# Serial_Wire_Debug.net
KiCad netlist of a schematic drawn in Altium Designer
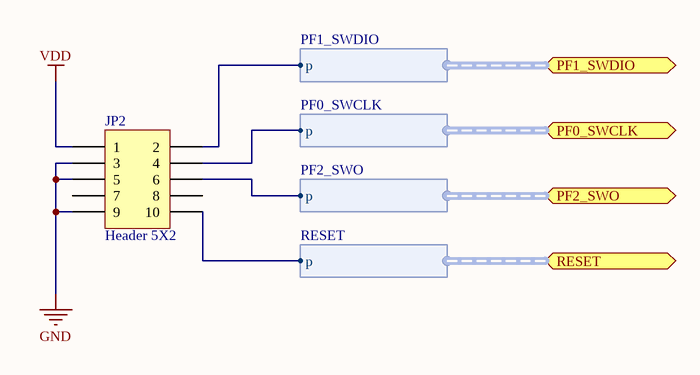
[diagram p0: Serial Wire Debug.SchDoc]

(export (version "E")
  (design (tool "Eeschema 10.0.6"))
  (components
    (comp (ref "JP2")
      (value "Header 5X2")
      (footprint "HDR2X5")
      (description "Header, 5-Pin, Dual row")
      (fields (field (name "PUBLISHER") "Altium Limited"))
      (libsource (lib "Miscellaneous Connectors") (part "Header 5X2"))
    )
  )
  (nets
    (net (code "9") (name "GND") (class "Default")
      (node (ref "JP2") (pin "3") (pinfunction "3_3") (pintype "passive"))
      (node (ref "JP2") (pin "5") (pinfunction "5_5") (pintype "passive"))
      (node (ref "JP2") (pin "9") (pinfunction "9_9") (pintype "passive"))
    )
    (net (code "10") (name "VDD") (class "Default")
      (node (ref "JP2") (pin "1") (pinfunction "1_1") (pintype "passive"))
    )
    (net (code "11") (name "unconnected-(JP2-Pad2)") (class "Default")
      (node (ref "JP2") (pin "2") (pinfunction "2_2") (pintype "passive"))
    )
    (net (code "12") (name "unconnected-(JP2-Pad4)") (class "Default")
      (node (ref "JP2") (pin "4") (pinfunction "4_4") (pintype "passive"))
    )
    (net (code "13") (name "unconnected-(JP2-Pad6)") (class "Default")
      (node (ref "JP2") (pin "6") (pinfunction "6_6") (pintype "passive"))
    )
    (net (code "14") (name "unconnected-(JP2-Pad7)") (class "Default")
      (node (ref "JP2") (pin "7") (pinfunction "7_7") (pintype "passive"))
    )
    (net (code "15") (name "unconnected-(JP2-Pad8)") (class "Default")
      (node (ref "JP2") (pin "8") (pinfunction "8_8") (pintype "passive"))
    )
    (net (code "16") (name "unconnected-(JP2-Pad10)") (class "Default")
      (node (ref "JP2") (pin "10") (pinfunction "10_10") (pintype "passive"))
    )
  )
)
